# brick_3pin_led_3x1.net
KiCad netlist of a schematic drawn in EAGLE
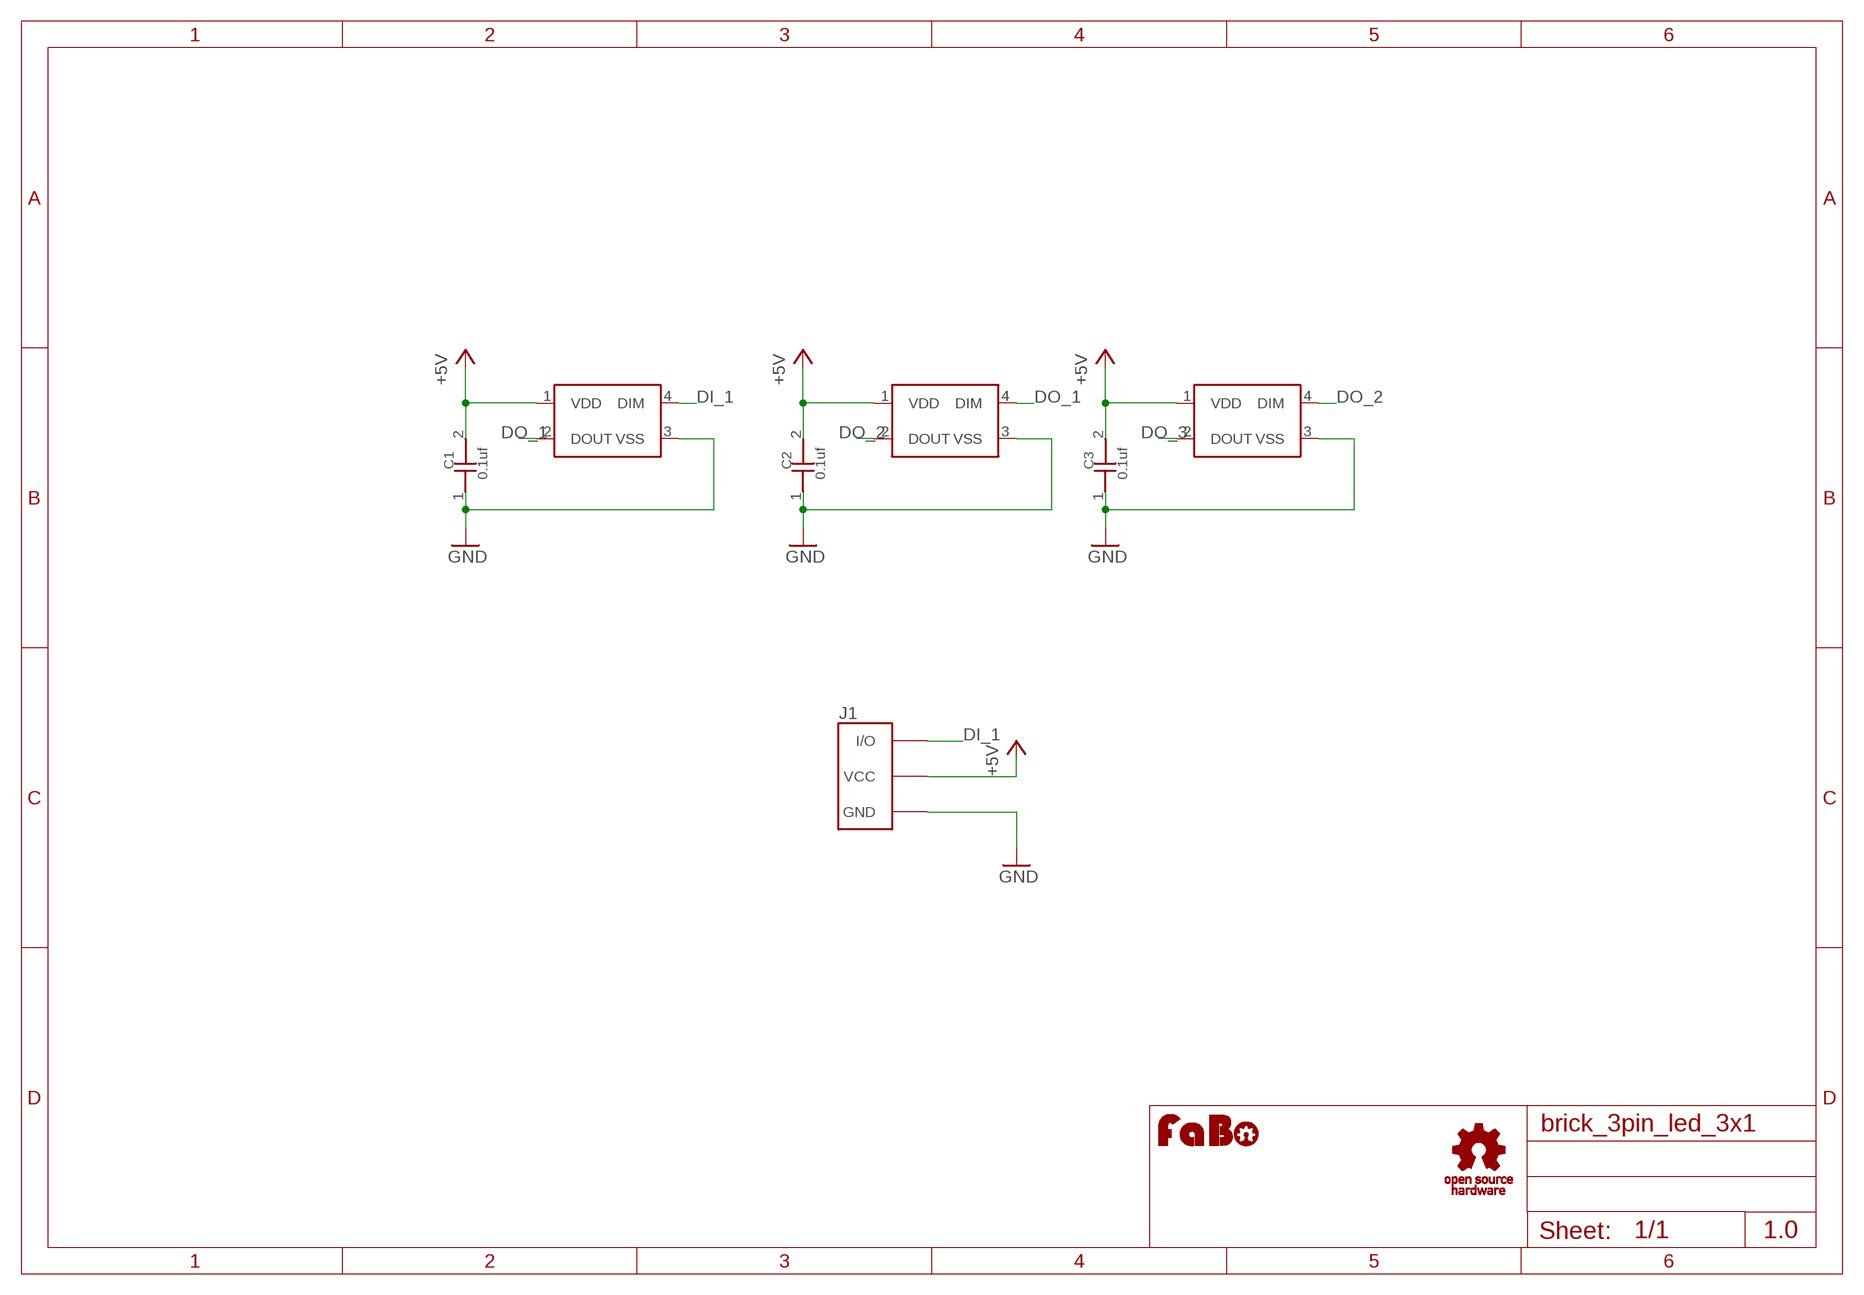
[diagram p0: schematic, sheet 1]

(export (version "E")
  (design (tool "Eeschema 10.0.6"))
  (components
    (comp (ref "C1")
      (value "0.1uf")
      (footprint "eagle-import:0603")
      (libsource (lib "eagle-import") (part "CAPACITOR0603"))
    )
    (comp (ref "C2")
      (value "0.1uf")
      (footprint "eagle-import:0603")
      (libsource (lib "eagle-import") (part "CAPACITOR0603"))
    )
    (comp (ref "C3")
      (value "0.1uf")
      (footprint "eagle-import:0603")
      (libsource (lib "eagle-import") (part "CAPACITOR0603"))
    )
    (comp (ref "J1")
      (value "BRICK_3PIN_MIDDLE")
      (footprint "eagle-import:BRICK_3PIN_MIDDLE")
      (libsource (lib "eagle-import") (part "BRICK_3PIN_MIDDLE"))
    )
    (comp (ref "LED1")
      (value "WS2818B")
      (footprint "eagle-import:WS2818B")
      (libsource (lib "eagle-import") (part "WS2818B"))
    )
    (comp (ref "LED2")
      (value "WS2818B")
      (footprint "eagle-import:WS2818B")
      (libsource (lib "eagle-import") (part "WS2818B"))
    )
    (comp (ref "LED3")
      (value "WS2818B")
      (footprint "eagle-import:WS2818B")
      (libsource (lib "eagle-import") (part "WS2818B"))
    )
    (comp (ref "U$4")
      (value "LOGO_FABO-M")
      (footprint "eagle-import:LOGO_FABO_M")
      (libsource (lib "eagle-import") (part "LOGO_FABO-M"))
    )
    (comp (ref "U$5")
      (value "LOGO_OSHW_T-M")
      (footprint "eagle-import:LOGO_OSHW_T_M")
      (libsource (lib "eagle-import") (part "LOGO_OSHW_T-M"))
    )
  )
  (nets
    (net (code "1") (name "+5V") (class "Default")
      (node (ref "C1") (pin "2") (pinfunction "2_2") (pintype "passive"))
      (node (ref "C2") (pin "2") (pinfunction "2_2") (pintype "passive"))
      (node (ref "C3") (pin "2") (pinfunction "2_2") (pintype "passive"))
      (node (ref "J1") (pin "VCC") (pinfunction "VCC_VCC") (pintype "bidirectional"))
      (node (ref "LED1") (pin "1") (pinfunction "VDD_1") (pintype "bidirectional"))
      (node (ref "LED2") (pin "1") (pinfunction "VDD_1") (pintype "bidirectional"))
      (node (ref "LED3") (pin "1") (pinfunction "VDD_1") (pintype "bidirectional"))
    )
    (net (code "2") (name "/DI_1") (class "Default")
      (node (ref "J1") (pin "IN/OUT") (pinfunction "I/O_IN/OUT") (pintype "bidirectional"))
      (node (ref "LED1") (pin "4") (pinfunction "DIM_4") (pintype "bidirectional"))
    )
    (net (code "3") (name "/DO_1") (class "Default")
      (node (ref "LED1") (pin "2") (pinfunction "DOUT_2") (pintype "bidirectional"))
      (node (ref "LED2") (pin "4") (pinfunction "DIM_4") (pintype "bidirectional"))
    )
    (net (code "4") (name "/DO_2") (class "Default")
      (node (ref "LED2") (pin "2") (pinfunction "DOUT_2") (pintype "bidirectional"))
      (node (ref "LED3") (pin "4") (pinfunction "DIM_4") (pintype "bidirectional"))
    )
    (net (code "5") (name "/DO_3") (class "Default")
      (node (ref "LED3") (pin "2") (pinfunction "DOUT_2") (pintype "bidirectional"))
    )
    (net (code "6") (name "GND") (class "Default")
      (node (ref "C1") (pin "1") (pinfunction "1_1") (pintype "passive"))
      (node (ref "C2") (pin "1") (pinfunction "1_1") (pintype "passive"))
      (node (ref "C3") (pin "1") (pinfunction "1_1") (pintype "passive"))
      (node (ref "J1") (pin "GND") (pinfunction "GND_GND") (pintype "bidirectional"))
      (node (ref "LED1") (pin "3") (pinfunction "VSS_3") (pintype "bidirectional"))
      (node (ref "LED2") (pin "3") (pinfunction "VSS_3") (pintype "bidirectional"))
      (node (ref "LED3") (pin "3") (pinfunction "VSS_3") (pintype "bidirectional"))
    )
  )
)
